# VoltageRef.net
KiCad netlist of a schematic drawn in Altium Designer
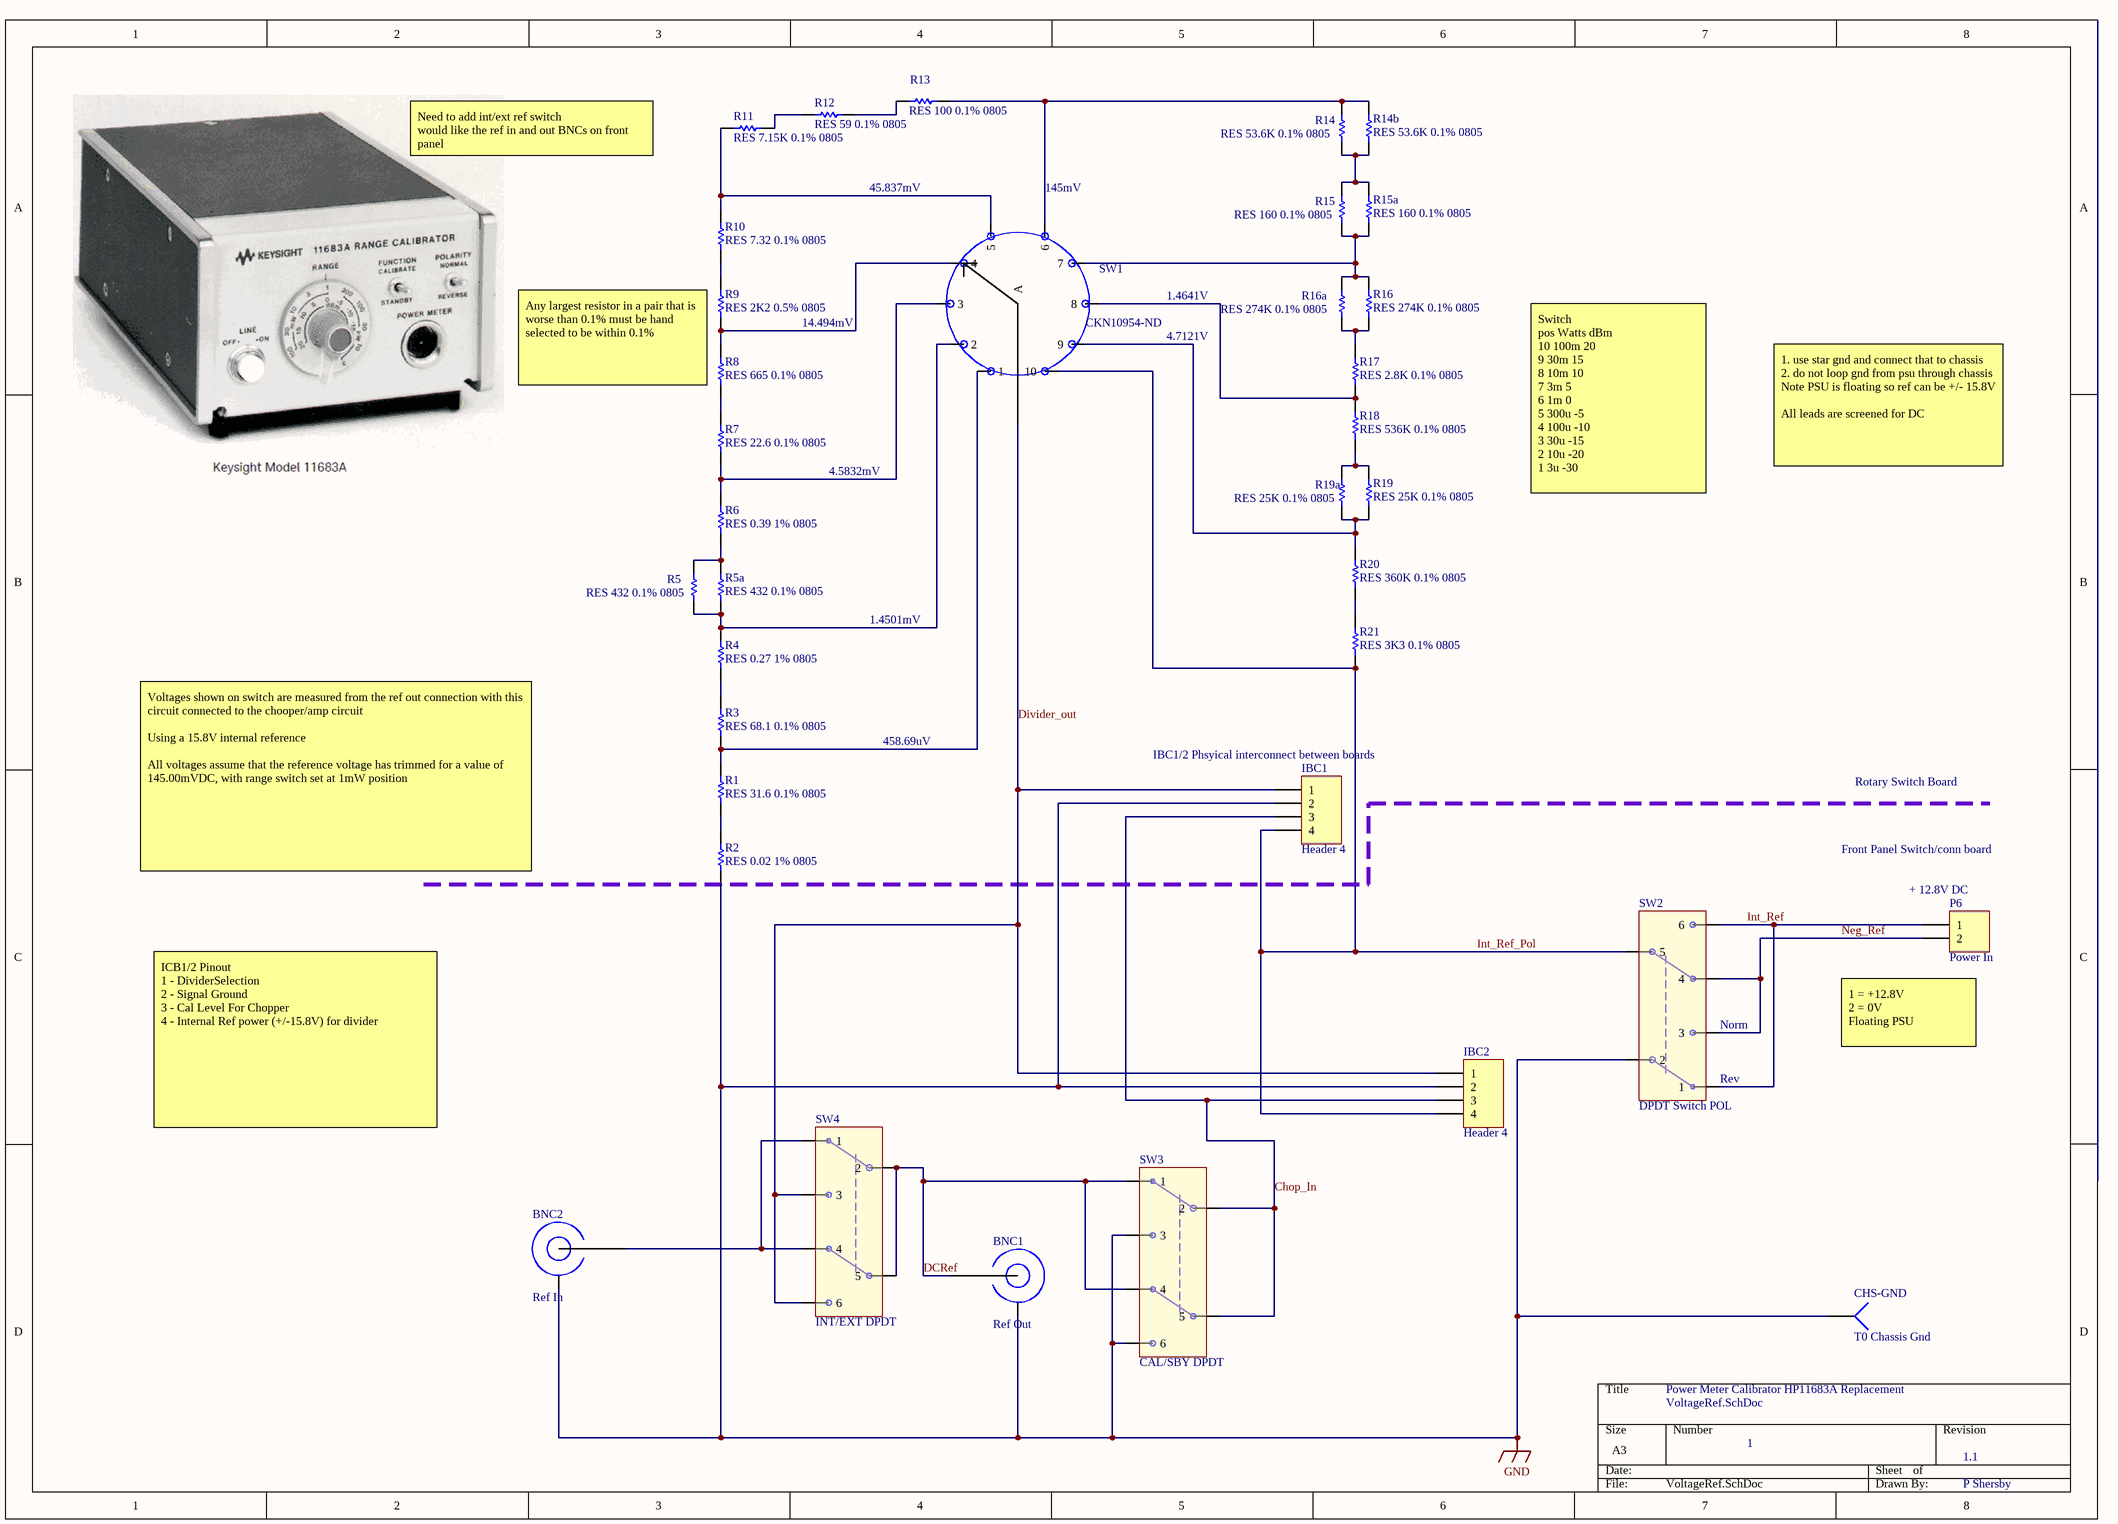
[diagram p0: VoltageRef.SchDoc]

(export (version "E")
  (design (tool "Eeschema 10.0.6"))
  (components
    (comp (ref "BNC1")
      (value "Ref Out")
      (footprint "BNC PCB Plastic")
      (description "BNC PCB Mount")
      (libsource (lib "Mechanical") (part "BNC PCB"))
    )
    (comp (ref "BNC2")
      (value "Ref In")
      (footprint "BNC PCB Plastic")
      (description "BNC Ref Out")
      (libsource (lib "") (part "BNC PCB_1"))
    )
    (comp (ref "CHS-GND")
      (value "T0 Chassis Gnd")
      (footprint "PIN1")
      (description "Socket")
      (fields (field (name "PUBLISHER") "Altium Limited"))
      (libsource (lib "Miscellaneous Connectors") (part "Socket"))
    )
    (comp (ref "IBC1")
      (value "Header 4")
      (footprint "HDR1X4")
      (description "Header, 4-Pin")
      (fields (field (name "PUBLISHER") "Altium Limited"))
      (libsource (lib "Miscellaneous Connectors") (part "Header 4"))
    )
    (comp (ref "IBC2")
      (value "Header 4")
      (footprint "HDR1X4")
      (description "Header, 4-Pin")
      (fields (field (name "PUBLISHER") "Altium Limited"))
      (libsource (lib "Miscellaneous Connectors") (part "Header 4"))
    )
    (comp (ref "P6")
      (value "Power In")
      (footprint "HDR1X2")
      (description "Header, 2-Pin")
      (fields (field (name "PUBLISHER") "Altium Limited"))
      (libsource (lib "Miscellaneous Connectors") (part "Header 2"))
    )
    (comp (ref "R1")
      (value "RES 31.6 0.1% 0805")
      (footprint "RESC2013X70X40LL20T20")
      (description "Resistor 31.6 0.1% 0805  0.2W 10ppm/C")
      (fields (field (name "MANUFACTURER") "Panasonic"))
      (libsource (lib "Altium Content Vault") (part "CMP-2001-00110-5"))
    )
    (comp (ref "R2")
      (value "RES 0.02 1% 0805")
      (footprint "RESC2013X70X40LL20T20")
      (description "Resistor 0.02 1% 0805  0.5W 50ppm/C")
      (fields (field (name "MANUFACTURER") "Panasonic"))
      (libsource (lib "Altium Content Vault") (part "CMP-2001-00110-5"))
    )
    (comp (ref "R3")
      (value "RES 68.1 0.1% 0805")
      (footprint "RESC2013X70X40LL20T20")
      (description "Resistor 68.1 0.1% 0805  0.2W 10ppm/C")
      (fields (field (name "MANUFACTURER") "Panasonic"))
      (libsource (lib "Altium Content Vault") (part "CMP-2001-00110-5"))
    )
    (comp (ref "R4")
      (value "RES 0.27 1% 0805")
      (footprint "RESC2013X70X40LL20T20")
      (description "Resistor 0.27 1% 0805  0.2W 10ppm/C")
      (fields (field (name "MANUFACTURER") "Panasonic"))
      (libsource (lib "Altium Content Vault") (part "CMP-2001-00110-5"))
    )
    (comp (ref "R5")
      (value "RES 432 0.1% 0805")
      (footprint "RESC2013X70X40LL20T20")
      (description "Resistor 432 0.1% 0805  0.2W 10ppm/C")
      (fields (field (name "MANUFACTURER") "Panasonic"))
      (libsource (lib "Altium Content Vault") (part "CMP-2001-00110-5"))
    )
    (comp (ref "R5a")
      (value "RES 432 0.1% 0805")
      (footprint "RESC2013X70X40LL20T20")
      (description "Resistor 432 0.1% 0805  0.2W 10ppm/C")
      (fields (field (name "MANUFACTURER") "Panasonic"))
      (libsource (lib "Altium Content Vault") (part "CMP-2001-00110-5"))
    )
    (comp (ref "R6")
      (value "RES 0.39 1% 0805")
      (footprint "RESC2013X70X40LL20T20")
      (description "Resistor 0.39 1% 0805  0.2W 10ppm/C")
      (fields (field (name "MANUFACTURER") "Panasonic"))
      (libsource (lib "Altium Content Vault") (part "CMP-2001-00110-5"))
    )
    (comp (ref "R7")
      (value "RES 22.6 0.1% 0805")
      (footprint "RESC2013X70X40LL20T20")
      (description "Resistor 22.6 0.1% 0805  0.2W 10ppm/C")
      (fields (field (name "MANUFACTURER") "Panasonic"))
      (libsource (lib "Altium Content Vault") (part "CMP-2001-00110-5"))
    )
    (comp (ref "R8")
      (value "RES 665 0.1% 0805")
      (footprint "RESC2013X70X40LL20T20")
      (description "Resistor 665 0.1% 0805  0.2W 10ppm/C")
      (fields (field (name "MANUFACTURER") "Panasonic"))
      (libsource (lib "Altium Content Vault") (part "CMP-2001-00110-5"))
    )
    (comp (ref "R9")
      (value "RES 2K2 0.5% 0805")
      (footprint "RESC2013X70X40LL20T20")
      (description "Resistor 2K2 0.5%  0805  0.2W 10ppm/C")
      (fields (field (name "MANUFACTURER") "Panasonic"))
      (libsource (lib "Altium Content Vault") (part "CMP-2001-00110-5"))
    )
    (comp (ref "R10")
      (value "RES 7.32 0.1% 0805")
      (footprint "RESC2013X70X40LL20T20")
      (description "Resistor 7.32 0.1% 0805  0.2W 10ppm/C")
      (fields (field (name "MANUFACTURER") "Panasonic"))
      (libsource (lib "Altium Content Vault") (part "CMP-2001-00110-5"))
    )
    (comp (ref "R11")
      (value "RES 7.15K 0.1% 0805")
      (footprint "RESC2013X70X40LL20T20")
      (description "Resistor 7.15K 0.1% 0805  0.2W 10ppm/C")
      (fields (field (name "MANUFACTURER") "Panasonic"))
      (libsource (lib "Altium Content Vault") (part "CMP-2001-00110-5"))
    )
    (comp (ref "R12")
      (value "RES 59 0.1% 0805")
      (footprint "RESC2013X70X40LL20T20")
      (description "Resistor 59 0.1% 0805  0.2W 10ppm/C")
      (fields (field (name "MANUFACTURER") "Panasonic"))
      (libsource (lib "Altium Content Vault") (part "CMP-2001-00110-5"))
    )
    (comp (ref "R13")
      (value "RES 100 0.1% 0805")
      (footprint "RESC2013X70X40LL20T20")
      (description "Resistor 100 0.1% 0805  0.2W 10ppm/C")
      (fields (field (name "MANUFACTURER") "Panasonic"))
      (libsource (lib "Altium Content Vault") (part "CMP-2001-00110-5"))
    )
    (comp (ref "R14")
      (value "RES 53.6K 0.1% 0805")
      (footprint "RESC2013X70X40LL20T20")
      (description "Resistor 53.6K 0.1% 0805  0.2W 10ppm/C")
      (fields (field (name "MANUFACTURER") "Panasonic"))
      (libsource (lib "Altium Content Vault") (part "CMP-2001-00110-5"))
    )
    (comp (ref "R14b")
      (value "RES 53.6K 0.1% 0805")
      (footprint "RESC2013X70X40LL20T20")
      (description "Resistor 53.6K 0.1% 0805  0.2W 10ppm/C")
      (fields (field (name "MANUFACTURER") "Panasonic"))
      (libsource (lib "Altium Content Vault") (part "CMP-2001-00110-5"))
    )
    (comp (ref "R15")
      (value "RES 160 0.1% 0805")
      (footprint "RESC2013X70X40LL20T20")
      (description "Resistor 160 0.1% 0805  0.2W 10ppm/C")
      (fields (field (name "MANUFACTURER") "Panasonic"))
      (libsource (lib "Altium Content Vault") (part "CMP-2001-00110-5"))
    )
    (comp (ref "R15a")
      (value "RES 160 0.1% 0805")
      (footprint "RESC2013X70X40LL20T20")
      (description "Resistor 160 0.1% 0805  0.2W 10ppm/C")
      (fields (field (name "MANUFACTURER") "Panasonic"))
      (libsource (lib "Altium Content Vault") (part "CMP-2001-00110-5"))
    )
    (comp (ref "R16")
      (value "RES 274K 0.1% 0805")
      (footprint "RESC2013X70X40LL20T20")
      (description "Resistor 274K 0.1% 0805  0.2W 10ppm/C")
      (fields (field (name "MANUFACTURER") "Panasonic"))
      (libsource (lib "Altium Content Vault") (part "CMP-2001-00110-5"))
    )
    (comp (ref "R16a")
      (value "RES 274K 0.1% 0805")
      (footprint "RESC2013X70X40LL20T20")
      (description "Resistor 274K 0.1% 0805  0.2W 10ppm/C")
      (fields (field (name "MANUFACTURER") "Panasonic"))
      (libsource (lib "Altium Content Vault") (part "CMP-2001-00110-5"))
    )
    (comp (ref "R17")
      (value "RES 2.8K 0.1% 0805")
      (footprint "RESC2013X70X40LL20T20")
      (description "Resistor 2.8K 0.1% 0805  0.2W 10ppm/C")
      (fields (field (name "MANUFACTURER") "Panasonic"))
      (libsource (lib "Altium Content Vault") (part "CMP-2001-00110-5"))
    )
    (comp (ref "R18")
      (value "RES 536K 0.1% 0805")
      (footprint "RESC2013X70X40LL20T20")
      (description "Resistor 536K 0.1% 0805  1/8W 10ppm/C")
      (fields (field (name "MANUFACTURER") "Panasonic"))
      (libsource (lib "Altium Content Vault") (part "CMP-2001-00110-5"))
    )
    (comp (ref "R19")
      (value "RES 25K 0.1% 0805")
      (footprint "RESC2013X70X40LL20T20")
      (description "Resistor 25K 0.1% 0805  0.1W 10ppm/C")
      (fields (field (name "MANUFACTURER") "Panasonic"))
      (libsource (lib "Altium Content Vault") (part "CMP-2001-00110-5"))
    )
    (comp (ref "R19a")
      (value "RES 25K 0.1% 0805")
      (footprint "RESC2013X70X40LL20T20")
      (description "Resistor 25K 0.1% 0805  0.1W 10ppm/C")
      (fields (field (name "MANUFACTURER") "Panasonic"))
      (libsource (lib "Altium Content Vault") (part "CMP-2001-00110-5"))
    )
    (comp (ref "R20")
      (value "RES 360K 0.1% 0805")
      (footprint "RESC2013X70X40LL20T20")
      (description "Resistor 360K 0.1% 0805  1/8W 10ppm/C")
      (fields (field (name "MANUFACTURER") "Panasonic"))
      (libsource (lib "Altium Content Vault") (part "CMP-2001-00110-5"))
    )
    (comp (ref "R21")
      (value "RES 3K3 0.1% 0805")
      (footprint "RESC2013X70X40LL20T20")
      (description "Resistor 3K3 0.1% 0805  0.2W 10ppm/C")
      (fields (field (name "MANUFACTURER") "Panasonic"))
      (libsource (lib "Altium Content Vault") (part "CMP-2001-00110-5"))
    )
    (comp (ref "SW1")
      (value "Rotary Switch 10way")
      (footprint "SW_ROT_4x12")
      (description "Rotary Switch 10way PCB CKN10954-ND")
      (fields (field (name "PART NUMBER") "CKN10954-ND"))
      (libsource (lib "Mechanical") (part "Rotary_Switch_1x10"))
    )
    (comp (ref "SW2")
      (value "DPDT Switch POL")
      (footprint "DPDT Toggle E switch")
      (description "DPDT Switch")
      (libsource (lib "") (part "DPDT Switch_1"))
    )
    (comp (ref "SW3")
      (value "CAL/SBY DPDT")
      (footprint "DPDT Toggle E switch")
      (description "CAL/SDBY DPDT")
      (libsource (lib "Mechanical") (part "DPDT Switch"))
    )
    (comp (ref "SW4")
      (value "INT/EXT DPDT")
      (footprint "DPDT Toggle E switch")
      (description "DPDT Switch")
      (libsource (lib "Mechanical") (part "DPDT Switch"))
    )
  )
  (nets
    (net (code "1") (name "/Chop_In") (class "Default")
      (node (ref "IBC1") (pin "3") (pinfunction "3_3") (pintype "passive"))
      (node (ref "IBC2") (pin "3") (pinfunction "3_3") (pintype "passive"))
      (node (ref "SW3") (pin "2") (pinfunction "2_2") (pintype "passive"))
      (node (ref "SW3") (pin "5") (pinfunction "5_5") (pintype "passive"))
    )
    (net (code "2") (name "/DCRef") (class "Default")
      (node (ref "BNC1") (pin "1") (pinfunction "Signal_1") (pintype "passive"))
      (node (ref "SW3") (pin "1") (pinfunction "1_1") (pintype "passive"))
      (node (ref "SW3") (pin "4") (pinfunction "4_4") (pintype "passive"))
      (node (ref "SW4") (pin "2") (pinfunction "2_2") (pintype "passive"))
      (node (ref "SW4") (pin "5") (pinfunction "5_5") (pintype "passive"))
    )
    (net (code "3") (name "/Divider_out") (class "Default")
      (node (ref "IBC1") (pin "1") (pinfunction "1_1") (pintype "passive"))
      (node (ref "IBC2") (pin "1") (pinfunction "1_1") (pintype "passive"))
      (node (ref "SW1") (pin "A") (pinfunction "A_A") (pintype "passive"))
      (node (ref "SW4") (pin "3") (pinfunction "3_3") (pintype "passive"))
      (node (ref "SW4") (pin "6") (pinfunction "6_6") (pintype "passive"))
    )
    (net (code "4") (name "/Int_Ref") (class "Default")
      (node (ref "P6") (pin "1") (pinfunction "1_1") (pintype "passive"))
      (node (ref "SW2") (pin "1") (pinfunction "1_1") (pintype "passive"))
      (node (ref "SW2") (pin "6") (pinfunction "6_6") (pintype "passive"))
    )
    (net (code "5") (name "/Int_Ref_Pol") (class "Default")
      (node (ref "IBC1") (pin "4") (pinfunction "4_4") (pintype "passive"))
      (node (ref "IBC2") (pin "4") (pinfunction "4_4") (pintype "passive"))
      (node (ref "R21") (pin "1") (pinfunction "1_1") (pintype "passive"))
      (node (ref "SW1") (pin "10") (pinfunction "10_10") (pintype "passive"))
      (node (ref "SW2") (pin "5") (pinfunction "5_5") (pintype "passive"))
    )
    (net (code "6") (name "/Neg_Ref") (class "Default")
      (node (ref "P6") (pin "2") (pinfunction "2_2") (pintype "passive"))
      (node (ref "SW2") (pin "3") (pinfunction "3_3") (pintype "passive"))
      (node (ref "SW2") (pin "4") (pinfunction "4_4") (pintype "passive"))
    )
    (net (code "7") (name "GND") (class "Default")
      (node (ref "BNC1") (pin "2") (pinfunction "Gnd_2") (pintype "passive"))
      (node (ref "BNC2") (pin "2") (pinfunction "Gnd_2") (pintype "passive"))
      (node (ref "CHS-GND") (pin "1") (pinfunction "1_1") (pintype "passive"))
      (node (ref "IBC1") (pin "2") (pinfunction "2_2") (pintype "passive"))
      (node (ref "IBC2") (pin "2") (pinfunction "2_2") (pintype "passive"))
      (node (ref "R2") (pin "1") (pinfunction "1_1") (pintype "passive"))
      (node (ref "SW2") (pin "2") (pinfunction "2_2") (pintype "passive"))
      (node (ref "SW3") (pin "3") (pinfunction "3_3") (pintype "passive"))
      (node (ref "SW3") (pin "6") (pinfunction "6_6") (pintype "passive"))
    )
    (net (code "8") (name "Net-(BNC2-Signal)") (class "Default")
      (node (ref "BNC2") (pin "1") (pinfunction "Signal_1") (pintype "passive"))
      (node (ref "SW4") (pin "1") (pinfunction "1_1") (pintype "passive"))
      (node (ref "SW4") (pin "4") (pinfunction "4_4") (pintype "passive"))
    )
    (net (code "9") (name "Net-(R1-Pad1)") (class "Default")
      (node (ref "R1") (pin "1") (pinfunction "1_1") (pintype "passive"))
      (node (ref "R2") (pin "2") (pinfunction "2_2") (pintype "passive"))
    )
    (net (code "10") (name "Net-(R1-Pad2)") (class "Default")
      (node (ref "R1") (pin "2") (pinfunction "2_2") (pintype "passive"))
      (node (ref "R3") (pin "1") (pinfunction "1_1") (pintype "passive"))
      (node (ref "SW1") (pin "1") (pinfunction "1_1") (pintype "passive"))
    )
    (net (code "11") (name "Net-(R3-Pad2)") (class "Default")
      (node (ref "R3") (pin "2") (pinfunction "2_2") (pintype "passive"))
      (node (ref "R4") (pin "1") (pinfunction "1_1") (pintype "passive"))
    )
    (net (code "12") (name "Net-(R4-Pad2)") (class "Default")
      (node (ref "R4") (pin "2") (pinfunction "2_2") (pintype "passive"))
      (node (ref "R5") (pin "1") (pinfunction "1_1") (pintype "passive"))
      (node (ref "R5a") (pin "1") (pinfunction "1_1") (pintype "passive"))
      (node (ref "SW1") (pin "2") (pinfunction "2_2") (pintype "passive"))
    )
    (net (code "13") (name "Net-(R5-Pad2)") (class "Default")
      (node (ref "R5") (pin "2") (pinfunction "2_2") (pintype "passive"))
      (node (ref "R5a") (pin "2") (pinfunction "2_2") (pintype "passive"))
      (node (ref "R6") (pin "1") (pinfunction "1_1") (pintype "passive"))
    )
    (net (code "14") (name "Net-(R6-Pad2)") (class "Default")
      (node (ref "R6") (pin "2") (pinfunction "2_2") (pintype "passive"))
      (node (ref "R7") (pin "1") (pinfunction "1_1") (pintype "passive"))
      (node (ref "SW1") (pin "3") (pinfunction "3_3") (pintype "passive"))
    )
    (net (code "15") (name "Net-(R7-Pad2)") (class "Default")
      (node (ref "R7") (pin "2") (pinfunction "2_2") (pintype "passive"))
      (node (ref "R8") (pin "1") (pinfunction "1_1") (pintype "passive"))
    )
    (net (code "16") (name "Net-(R8-Pad2)") (class "Default")
      (node (ref "R8") (pin "2") (pinfunction "2_2") (pintype "passive"))
      (node (ref "R9") (pin "1") (pinfunction "1_1") (pintype "passive"))
      (node (ref "SW1") (pin "4") (pinfunction "4_4") (pintype "passive"))
    )
    (net (code "17") (name "Net-(R10-Pad1)") (class "Default")
      (node (ref "R10") (pin "1") (pinfunction "1_1") (pintype "passive"))
      (node (ref "R9") (pin "2") (pinfunction "2_2") (pintype "passive"))
    )
    (net (code "18") (name "Net-(R10-Pad2)") (class "Default")
      (node (ref "R10") (pin "2") (pinfunction "2_2") (pintype "passive"))
      (node (ref "R11") (pin "1") (pinfunction "1_1") (pintype "passive"))
      (node (ref "SW1") (pin "5") (pinfunction "5_5") (pintype "passive"))
    )
    (net (code "19") (name "Net-(R11-Pad2)") (class "Default")
      (node (ref "R11") (pin "2") (pinfunction "2_2") (pintype "passive"))
      (node (ref "R12") (pin "1") (pinfunction "1_1") (pintype "passive"))
    )
    (net (code "20") (name "Net-(R12-Pad2)") (class "Default")
      (node (ref "R12") (pin "2") (pinfunction "2_2") (pintype "passive"))
      (node (ref "R13") (pin "1") (pinfunction "1_1") (pintype "passive"))
    )
    (net (code "21") (name "Net-(R13-Pad2)") (class "Default")
      (node (ref "R13") (pin "2") (pinfunction "2_2") (pintype "passive"))
      (node (ref "R14") (pin "2") (pinfunction "2_2") (pintype "passive"))
      (node (ref "R14b") (pin "2") (pinfunction "2_2") (pintype "passive"))
      (node (ref "SW1") (pin "6") (pinfunction "6_6") (pintype "passive"))
    )
    (net (code "22") (name "Net-(R14-Pad1)") (class "Default")
      (node (ref "R14") (pin "1") (pinfunction "1_1") (pintype "passive"))
      (node (ref "R14b") (pin "1") (pinfunction "1_1") (pintype "passive"))
      (node (ref "R15") (pin "2") (pinfunction "2_2") (pintype "passive"))
      (node (ref "R15a") (pin "2") (pinfunction "2_2") (pintype "passive"))
    )
    (net (code "23") (name "Net-(R15-Pad1)") (class "Default")
      (node (ref "R15") (pin "1") (pinfunction "1_1") (pintype "passive"))
      (node (ref "R15a") (pin "1") (pinfunction "1_1") (pintype "passive"))
      (node (ref "R16") (pin "2") (pinfunction "2_2") (pintype "passive"))
      (node (ref "R16a") (pin "2") (pinfunction "2_2") (pintype "passive"))
      (node (ref "SW1") (pin "7") (pinfunction "7_7") (pintype "passive"))
    )
    (net (code "24") (name "Net-(R16-Pad1)") (class "Default")
      (node (ref "R16") (pin "1") (pinfunction "1_1") (pintype "passive"))
      (node (ref "R16a") (pin "1") (pinfunction "1_1") (pintype "passive"))
      (node (ref "R17") (pin "2") (pinfunction "2_2") (pintype "passive"))
    )
    (net (code "25") (name "Net-(R17-Pad1)") (class "Default")
      (node (ref "R17") (pin "1") (pinfunction "1_1") (pintype "passive"))
      (node (ref "R18") (pin "2") (pinfunction "2_2") (pintype "passive"))
      (node (ref "SW1") (pin "8") (pinfunction "8_8") (pintype "passive"))
    )
    (net (code "26") (name "Net-(R18-Pad1)") (class "Default")
      (node (ref "R18") (pin "1") (pinfunction "1_1") (pintype "passive"))
      (node (ref "R19") (pin "2") (pinfunction "2_2") (pintype "passive"))
      (node (ref "R19a") (pin "2") (pinfunction "2_2") (pintype "passive"))
    )
    (net (code "27") (name "Net-(R19-Pad1)") (class "Default")
      (node (ref "R19") (pin "1") (pinfunction "1_1") (pintype "passive"))
      (node (ref "R19a") (pin "1") (pinfunction "1_1") (pintype "passive"))
      (node (ref "R20") (pin "2") (pinfunction "2_2") (pintype "passive"))
      (node (ref "SW1") (pin "9") (pinfunction "9_9") (pintype "passive"))
    )
    (net (code "28") (name "Net-(R20-Pad1)") (class "Default")
      (node (ref "R20") (pin "1") (pinfunction "1_1") (pintype "passive"))
      (node (ref "R21") (pin "2") (pinfunction "2_2") (pintype "passive"))
    )
  )
)
